# control_module.net
KiCad netlist of a schematic drawn in EAGLE
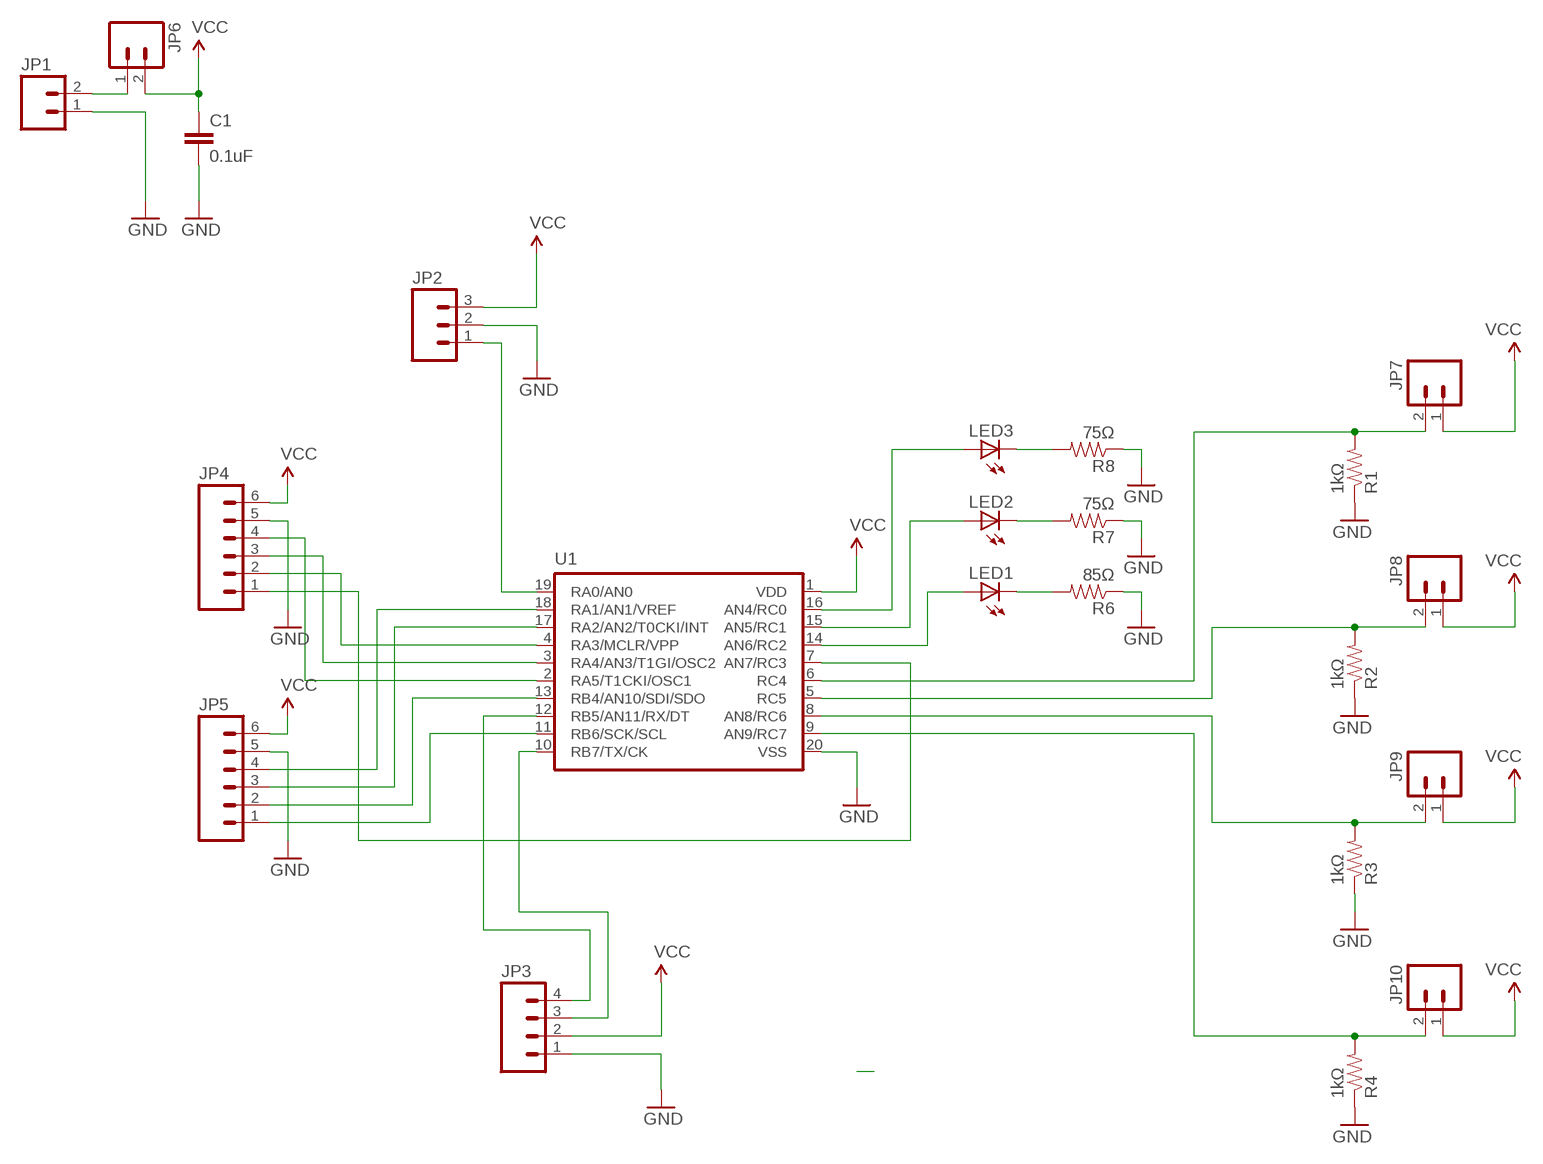
[diagram p0: schematic, sheet 1]

(export (version "E")
  (design (tool "Eeschema 10.0.6"))
  (components
    (comp (ref "C1")
      (value "0.1uF")
      (footprint "eagle-import:CAP-PTH-5MM")
      (libsource (lib "eagle-import") (part "CAPPTH1"))
    )
    (comp (ref "JP1")
      (value "M02PTH")
      (footprint "eagle-import:1X02")
      (libsource (lib "eagle-import") (part "M02PTH"))
    )
    (comp (ref "JP2")
      (value "M03PTH")
      (footprint "eagle-import:1X03")
      (libsource (lib "eagle-import") (part "M03PTH"))
    )
    (comp (ref "JP3")
      (value "M04PTH")
      (footprint "eagle-import:1X04")
      (libsource (lib "eagle-import") (part "M04PTH"))
    )
    (comp (ref "JP4")
      (value "M06SILK_FEMALE_PTH")
      (footprint "eagle-import:1X06")
      (libsource (lib "eagle-import") (part "M06SILK_FEMALE_PTH"))
    )
    (comp (ref "JP5")
      (value "M06SILK_FEMALE_PTH")
      (footprint "eagle-import:1X06")
      (libsource (lib "eagle-import") (part "M06SILK_FEMALE_PTH"))
    )
    (comp (ref "JP6")
      (value "M02PTH")
      (footprint "eagle-import:1X02")
      (libsource (lib "eagle-import") (part "M02PTH"))
    )
    (comp (ref "JP7")
      (value "M02PTH")
      (footprint "eagle-import:1X02")
      (libsource (lib "eagle-import") (part "M02PTH"))
    )
    (comp (ref "JP8")
      (value "M02PTH")
      (footprint "eagle-import:1X02")
      (libsource (lib "eagle-import") (part "M02PTH"))
    )
    (comp (ref "JP9")
      (value "M02PTH")
      (footprint "eagle-import:1X02")
      (libsource (lib "eagle-import") (part "M02PTH"))
    )
    (comp (ref "JP10")
      (value "M02PTH")
      (footprint "eagle-import:1X02")
      (libsource (lib "eagle-import") (part "M02PTH"))
    )
    (comp (ref "LED1")
      (value "LED3MM")
      (footprint "eagle-import:LED3MM")
      (libsource (lib "eagle-import") (part "LED3MM"))
    )
    (comp (ref "LED2")
      (value "LED3MM")
      (footprint "eagle-import:LED3MM")
      (libsource (lib "eagle-import") (part "LED3MM"))
    )
    (comp (ref "LED3")
      (value "LED3MM")
      (footprint "eagle-import:LED3MM")
      (libsource (lib "eagle-import") (part "LED3MM"))
    )
    (comp (ref "R1")
      (value "1kΩ")
      (footprint "eagle-import:AXIAL-0.4")
      (libsource (lib "eagle-import") (part "RESISTORPTH-1/4W"))
    )
    (comp (ref "R2")
      (value "1kΩ")
      (footprint "eagle-import:AXIAL-0.4")
      (libsource (lib "eagle-import") (part "RESISTORPTH-1/4W"))
    )
    (comp (ref "R3")
      (value "1kΩ")
      (footprint "eagle-import:AXIAL-0.4")
      (libsource (lib "eagle-import") (part "RESISTORPTH-1/4W"))
    )
    (comp (ref "R4")
      (value "1kΩ")
      (footprint "eagle-import:AXIAL-0.4")
      (libsource (lib "eagle-import") (part "RESISTORPTH-1/4W"))
    )
    (comp (ref "R6")
      (value "85Ω")
      (footprint "eagle-import:AXIAL-0.4")
      (libsource (lib "eagle-import") (part "RESISTORPTH-1/4W"))
    )
    (comp (ref "R7")
      (value "75Ω")
      (footprint "eagle-import:AXIAL-0.4")
      (libsource (lib "eagle-import") (part "RESISTORPTH-1/4W"))
    )
    (comp (ref "R8")
      (value "75Ω")
      (footprint "eagle-import:AXIAL-0.4")
      (libsource (lib "eagle-import") (part "RESISTORPTH-1/4W"))
    )
    (comp (ref "U1")
      (value "PIC16F6XX")
      (footprint "eagle-import:DIL20")
      (libsource (lib "eagle-import") (part "PIC16F6XX"))
    )
  )
  (nets
    (net (code "1") (name "GND") (class "Default")
      (node (ref "C1") (pin "2") (pinfunction "2_2") (pintype "passive"))
      (node (ref "JP1") (pin "1") (pinfunction "1_1") (pintype "passive"))
      (node (ref "JP2") (pin "2") (pinfunction "2_2") (pintype "passive"))
      (node (ref "JP3") (pin "1") (pinfunction "1_1") (pintype "passive"))
      (node (ref "JP4") (pin "5") (pinfunction "5_5") (pintype "passive"))
      (node (ref "JP5") (pin "5") (pinfunction "5_5") (pintype "passive"))
      (node (ref "R1") (pin "P$1") (pinfunction "1_P$1") (pintype "passive"))
      (node (ref "R2") (pin "P$1") (pinfunction "1_P$1") (pintype "passive"))
      (node (ref "R3") (pin "P$1") (pinfunction "1_P$1") (pintype "passive"))
      (node (ref "R4") (pin "P$1") (pinfunction "1_P$1") (pintype "passive"))
      (node (ref "R6") (pin "P$1") (pinfunction "1_P$1") (pintype "passive"))
      (node (ref "R7") (pin "P$1") (pinfunction "1_P$1") (pintype "passive"))
      (node (ref "R8") (pin "P$1") (pinfunction "1_P$1") (pintype "passive"))
      (node (ref "U1") (pin "20") (pinfunction "VSS_20") (pintype "power_in"))
    )
    (net (code "2") (name "Net-(JP1-Pad2)") (class "Default")
      (node (ref "JP1") (pin "2") (pinfunction "2_2") (pintype "passive"))
      (node (ref "JP6") (pin "1") (pinfunction "1_1") (pintype "passive"))
    )
    (net (code "3") (name "Net-(LED1-C)") (class "Default")
      (node (ref "LED1") (pin "K") (pinfunction "C_K") (pintype "passive"))
      (node (ref "R6") (pin "P$2") (pinfunction "2_P$2") (pintype "passive"))
    )
    (net (code "4") (name "Net-(LED2-C)") (class "Default")
      (node (ref "LED2") (pin "K") (pinfunction "C_K") (pintype "passive"))
      (node (ref "R7") (pin "P$2") (pinfunction "2_P$2") (pintype "passive"))
    )
    (net (code "5") (name "Net-(LED3-C)") (class "Default")
      (node (ref "LED3") (pin "K") (pinfunction "C_K") (pintype "passive"))
      (node (ref "R8") (pin "P$2") (pinfunction "2_P$2") (pintype "passive"))
    )
    (net (code "6") (name "Net-(R1-2)") (class "Default")
      (node (ref "JP7") (pin "2") (pinfunction "2_2") (pintype "passive"))
      (node (ref "R1") (pin "P$2") (pinfunction "2_P$2") (pintype "passive"))
      (node (ref "U1") (pin "6") (pinfunction "RC4_6") (pintype "bidirectional"))
    )
    (net (code "7") (name "Net-(R2-2)") (class "Default")
      (node (ref "JP8") (pin "2") (pinfunction "2_2") (pintype "passive"))
      (node (ref "R2") (pin "P$2") (pinfunction "2_P$2") (pintype "passive"))
      (node (ref "U1") (pin "5") (pinfunction "RC5_5") (pintype "bidirectional"))
    )
    (net (code "8") (name "Net-(R3-2)") (class "Default")
      (node (ref "JP9") (pin "2") (pinfunction "2_2") (pintype "passive"))
      (node (ref "R3") (pin "P$2") (pinfunction "2_P$2") (pintype "passive"))
      (node (ref "U1") (pin "8") (pinfunction "AN8/RC6_8") (pintype "bidirectional"))
    )
    (net (code "9") (name "Net-(R4-2)") (class "Default")
      (node (ref "JP10") (pin "2") (pinfunction "2_2") (pintype "passive"))
      (node (ref "R4") (pin "P$2") (pinfunction "2_P$2") (pintype "passive"))
      (node (ref "U1") (pin "9") (pinfunction "AN9/RC7_9") (pintype "bidirectional"))
    )
    (net (code "10") (name "Net-(U1-AN4{slash}RC0)") (class "Default")
      (node (ref "LED3") (pin "A") (pinfunction "A_A") (pintype "passive"))
      (node (ref "U1") (pin "16") (pinfunction "AN4/RC0_16") (pintype "bidirectional"))
    )
    (net (code "11") (name "Net-(U1-AN5{slash}RC1)") (class "Default")
      (node (ref "LED2") (pin "A") (pinfunction "A_A") (pintype "passive"))
      (node (ref "U1") (pin "15") (pinfunction "AN5/RC1_15") (pintype "bidirectional"))
    )
    (net (code "12") (name "Net-(U1-AN6{slash}RC2)") (class "Default")
      (node (ref "LED1") (pin "A") (pinfunction "A_A") (pintype "passive"))
      (node (ref "U1") (pin "14") (pinfunction "AN6/RC2_14") (pintype "bidirectional"))
    )
    (net (code "13") (name "Net-(U1-AN7{slash}RC3)") (class "Default")
      (node (ref "JP4") (pin "1") (pinfunction "1_1") (pintype "passive"))
      (node (ref "U1") (pin "7") (pinfunction "AN7/RC3_7") (pintype "bidirectional"))
    )
    (net (code "14") (name "Net-(U1-RA0{slash}AN0)") (class "Default")
      (node (ref "JP2") (pin "1") (pinfunction "1_1") (pintype "passive"))
      (node (ref "U1") (pin "19") (pinfunction "RA0/AN0_19") (pintype "bidirectional"))
    )
    (net (code "15") (name "Net-(U1-RA1{slash}AN1{slash}VREF)") (class "Default")
      (node (ref "JP5") (pin "4") (pinfunction "4_4") (pintype "passive"))
      (node (ref "U1") (pin "18") (pinfunction "RA1/AN1/VREF_18") (pintype "bidirectional"))
    )
    (net (code "16") (name "Net-(U1-RA2{slash}AN2{slash}T0CKI{slash}INT)") (class "Default")
      (node (ref "JP5") (pin "3") (pinfunction "3_3") (pintype "passive"))
      (node (ref "U1") (pin "17") (pinfunction "RA2/AN2/T0CKI/INT_17") (pintype "bidirectional"))
    )
    (net (code "17") (name "Net-(U1-RA3{slash}MCLR{slash}VPP)") (class "Default")
      (node (ref "JP4") (pin "2") (pinfunction "2_2") (pintype "passive"))
      (node (ref "U1") (pin "4") (pinfunction "RA3/MCLR/VPP_4") (pintype "input"))
    )
    (net (code "18") (name "Net-(U1-RA4{slash}AN3{slash}T1GI{slash}OSC2)") (class "Default")
      (node (ref "JP4") (pin "3") (pinfunction "3_3") (pintype "passive"))
      (node (ref "U1") (pin "3") (pinfunction "RA4/AN3/T1GI/OSC2_3") (pintype "bidirectional"))
    )
    (net (code "19") (name "Net-(U1-RA5{slash}T1CKI{slash}OSC1)") (class "Default")
      (node (ref "JP4") (pin "4") (pinfunction "4_4") (pintype "passive"))
      (node (ref "U1") (pin "2") (pinfunction "RA5/T1CKI/OSC1_2") (pintype "bidirectional"))
    )
    (net (code "20") (name "Net-(U1-RB4{slash}AN10{slash}SDI{slash}SDO)") (class "Default")
      (node (ref "JP5") (pin "2") (pinfunction "2_2") (pintype "passive"))
      (node (ref "U1") (pin "13") (pinfunction "RB4/AN10/SDI/SDO_13") (pintype "bidirectional"))
    )
    (net (code "21") (name "Net-(U1-RB5{slash}AN11{slash}RX{slash}DT)") (class "Default")
      (node (ref "JP3") (pin "4") (pinfunction "4_4") (pintype "passive"))
      (node (ref "U1") (pin "12") (pinfunction "RB5/AN11/RX/DT_12") (pintype "bidirectional"))
    )
    (net (code "22") (name "Net-(U1-RB6{slash}SCK{slash}SCL)") (class "Default")
      (node (ref "JP5") (pin "1") (pinfunction "1_1") (pintype "passive"))
      (node (ref "U1") (pin "11") (pinfunction "RB6/SCK/SCL_11") (pintype "bidirectional"))
    )
    (net (code "23") (name "Net-(U1-RB7{slash}TX{slash}CK)") (class "Default")
      (node (ref "JP3") (pin "3") (pinfunction "3_3") (pintype "passive"))
      (node (ref "U1") (pin "10") (pinfunction "RB7/TX/CK_10") (pintype "bidirectional"))
    )
    (net (code "24") (name "VCC") (class "Default")
      (node (ref "C1") (pin "1") (pinfunction "1_1") (pintype "passive"))
      (node (ref "JP10") (pin "1") (pinfunction "1_1") (pintype "passive"))
      (node (ref "JP2") (pin "3") (pinfunction "3_3") (pintype "passive"))
      (node (ref "JP3") (pin "2") (pinfunction "2_2") (pintype "passive"))
      (node (ref "JP4") (pin "6") (pinfunction "6_6") (pintype "passive"))
      (node (ref "JP5") (pin "6") (pinfunction "6_6") (pintype "passive"))
      (node (ref "JP6") (pin "2") (pinfunction "2_2") (pintype "passive"))
      (node (ref "JP7") (pin "1") (pinfunction "1_1") (pintype "passive"))
      (node (ref "JP8") (pin "1") (pinfunction "1_1") (pintype "passive"))
      (node (ref "JP9") (pin "1") (pinfunction "1_1") (pintype "passive"))
      (node (ref "U1") (pin "1") (pinfunction "VDD_1") (pintype "power_in"))
    )
  )
)
